# AD637.net
KiCad netlist of a schematic drawn in Altium Designer
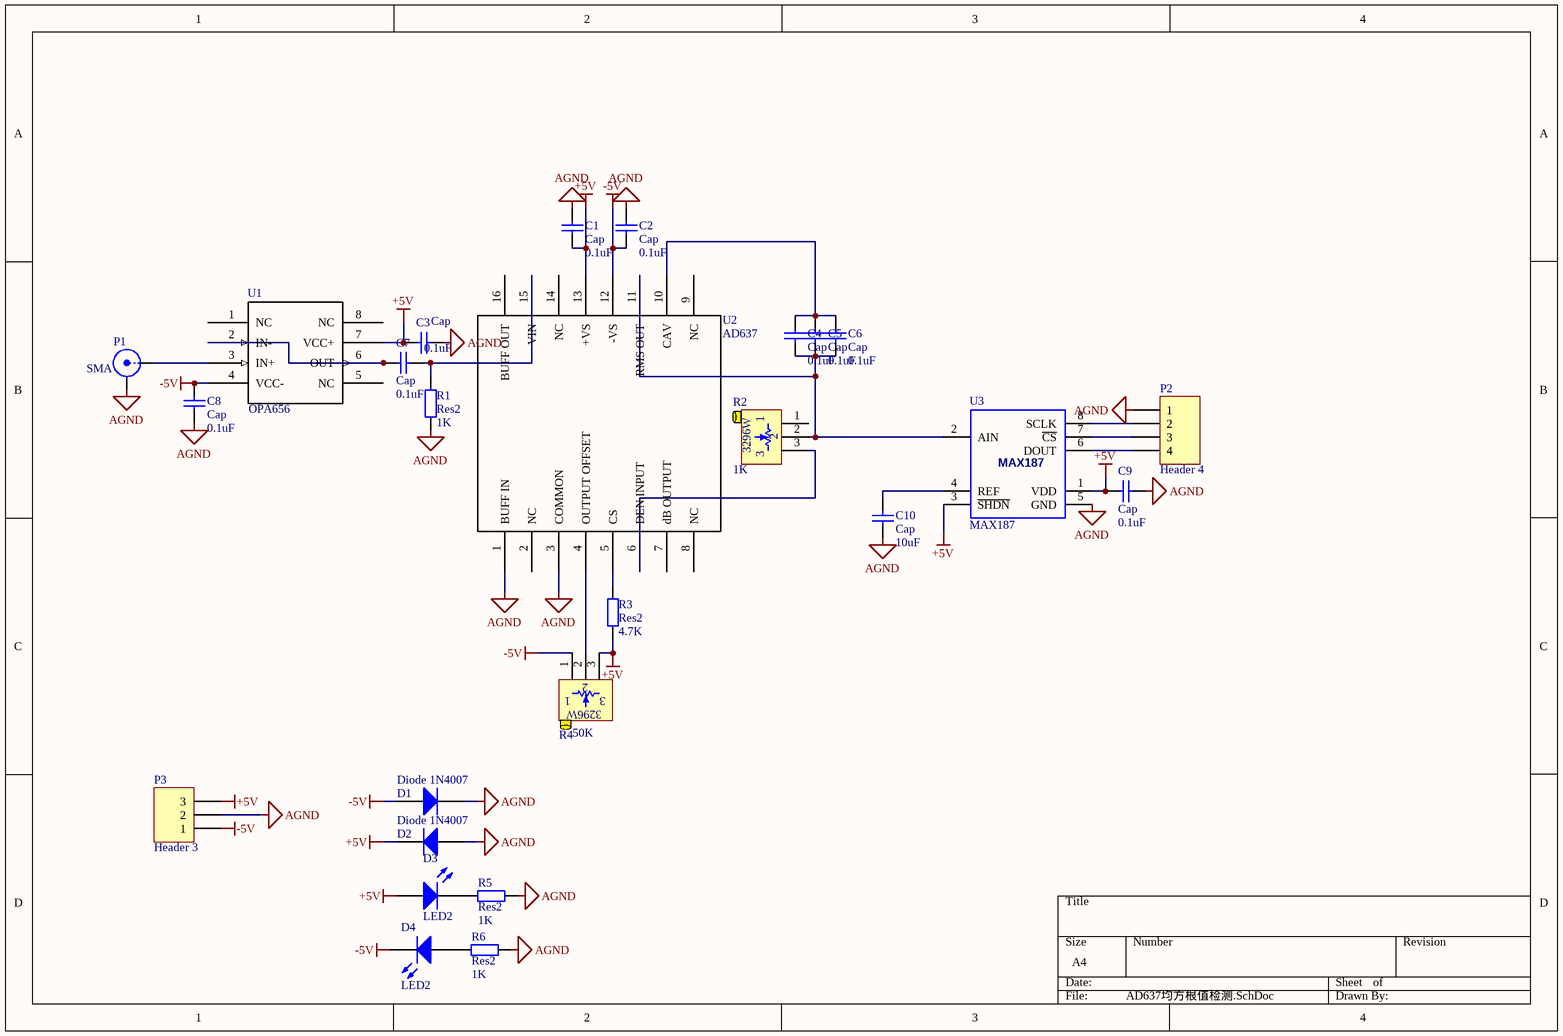
[diagram p0: AD637均方根值检测.SchDoc]

(export (version "E")
  (design (tool "Eeschema 10.0.6"))
  (components
    (comp (ref "C1")
      (value "Cap")
      (footprint "0805")
      (description "Capacitor")
      (fields (field (name "ALTIUM_VALUE") "0.1uF") (field (name "PUBLISHER") "Altium Limited"))
      (libsource (lib "Miscellaneous Devices") (part "Cap"))
    )
    (comp (ref "C2")
      (value "Cap")
      (footprint "0805")
      (description "Capacitor")
      (fields (field (name "ALTIUM_VALUE") "0.1uF") (field (name "PUBLISHER") "Altium Limited"))
      (libsource (lib "Miscellaneous Devices") (part "Cap"))
    )
    (comp (ref "C3")
      (value "Cap")
      (footprint "0805")
      (description "Capacitor")
      (fields (field (name "ALTIUM_VALUE") "0.1uF") (field (name "PUBLISHER") "Altium Limited"))
      (libsource (lib "Miscellaneous Devices") (part "Cap"))
    )
    (comp (ref "C4")
      (value "Cap")
      (footprint "0805")
      (description "Capacitor")
      (fields (field (name "ALTIUM_VALUE") "0.1uF") (field (name "PUBLISHER") "Altium Limited"))
      (libsource (lib "Miscellaneous Devices") (part "Cap"))
    )
    (comp (ref "C5")
      (value "Cap")
      (footprint "0805")
      (description "Capacitor")
      (fields (field (name "ALTIUM_VALUE") "0.1uF") (field (name "PUBLISHER") "Altium Limited"))
      (libsource (lib "Miscellaneous Devices") (part "Cap"))
    )
    (comp (ref "C6")
      (value "Cap")
      (footprint "0805")
      (description "Capacitor")
      (fields (field (name "ALTIUM_VALUE") "0.1uF") (field (name "PUBLISHER") "Altium Limited"))
      (libsource (lib "Miscellaneous Devices") (part "Cap"))
    )
    (comp (ref "C7")
      (value "Cap")
      (footprint "0805")
      (description "Capacitor")
      (fields (field (name "ALTIUM_VALUE") "0.1uF") (field (name "PUBLISHER") "Altium Limited"))
      (libsource (lib "Miscellaneous Devices") (part "Cap"))
    )
    (comp (ref "C8")
      (value "Cap")
      (footprint "0805")
      (description "Capacitor")
      (fields (field (name "ALTIUM_VALUE") "0.1uF") (field (name "PUBLISHER") "Altium Limited"))
      (libsource (lib "Miscellaneous Devices") (part "Cap"))
    )
    (comp (ref "C9")
      (value "Cap")
      (footprint "0805")
      (description "Capacitor")
      (fields (field (name "ALTIUM_VALUE") "0.1uF") (field (name "PUBLISHER") "Altium Limited"))
      (libsource (lib "Miscellaneous Devices") (part "Cap"))
    )
    (comp (ref "C10")
      (value "Cap")
      (footprint "0805")
      (description "Capacitor")
      (fields (field (name "ALTIUM_VALUE") "10uF") (field (name "PUBLISHER") "Altium Limited"))
      (libsource (lib "Miscellaneous Devices") (part "Cap"))
    )
    (comp (ref "D1")
      (value "Diode 1N4007")
      (footprint "0805")
      (description "1 Amp General Purpose Rectifier")
      (fields (field (name "PUBLISHER") "Altium Limited"))
      (libsource (lib "Miscellaneous Devices") (part "Diode 1N4007"))
    )
    (comp (ref "D2")
      (value "Diode 1N4007")
      (footprint "0805")
      (description "1 Amp General Purpose Rectifier")
      (fields (field (name "PUBLISHER") "Altium Limited"))
      (libsource (lib "Miscellaneous Devices") (part "Diode 1N4007"))
    )
    (comp (ref "D3")
      (value "LED2")
      (footprint "3.2X1.6X1.1")
      (description "Typical RED, GREEN, YELLOW, AMBER GaAs LED")
      (fields (field (name "PUBLISHER") "Altium Limited"))
      (libsource (lib "Miscellaneous Devices") (part "LED2"))
    )
    (comp (ref "D4")
      (value "LED2")
      (footprint "3.2X1.6X1.1")
      (description "Typical RED, GREEN, YELLOW, AMBER GaAs LED")
      (fields (field (name "PUBLISHER") "Altium Limited"))
      (libsource (lib "Miscellaneous Devices") (part "LED2"))
    )
    (comp (ref "P1") (value "SMA") (footprint "SMA") (libsource (lib "孙文丰") (part "SMA")))
    (comp (ref "P2")
      (value "Header 4")
      (footprint "HDR1X4")
      (description "Header, 4-Pin")
      (fields (field (name "PUBLISHER") "Altium Limited"))
      (libsource (lib "Miscellaneous Connectors") (part "Header 4"))
    )
    (comp (ref "P3")
      (value "Header 3")
      (footprint "3P排针")
      (description "Header, 3-Pin")
      (fields (field (name "PUBLISHER") "Altium Limited"))
      (libsource (lib "Miscellaneous Connectors") (part "Header 3"))
    )
    (comp (ref "R1")
      (value "Res2")
      (footprint "0805")
      (description "Resistor")
      (fields (field (name "ALTIUM_VALUE") "1K") (field (name "PUBLISHER") "Altium Limited"))
      (libsource (lib "Miscellaneous Devices") (part "Res2"))
    )
    (comp (ref "R2") (value "1K") (footprint "3P排针") (libsource (lib "") (part "电位器_3296W_1")))
    (comp (ref "R3")
      (value "Res2")
      (footprint "0805")
      (description "Resistor")
      (fields (field (name "ALTIUM_VALUE") "4.7K") (field (name "PUBLISHER") "Altium Limited"))
      (libsource (lib "") (part "Res2_2"))
    )
    (comp (ref "R4") (value "50K") (footprint "3P排针") (libsource (lib "常用器件集成库") (part "电位器_3296W")))
    (comp (ref "R5")
      (value "Res2")
      (footprint "0805")
      (description "Resistor")
      (fields (field (name "ALTIUM_VALUE") "1K") (field (name "PUBLISHER") "Altium Limited"))
      (libsource (lib "") (part "Res2_1"))
    )
    (comp (ref "R6")
      (value "Res2")
      (footprint "0805")
      (description "Resistor")
      (fields (field (name "ALTIUM_VALUE") "1K") (field (name "PUBLISHER") "Altium Limited"))
      (libsource (lib "") (part "Res2_1"))
    )
    (comp (ref "U1")
      (value "OPA656")
      (footprint "THS3001_SOIC")
      (libsource (lib "MY_TI_Library") (part "OPA656"))
    )
    (comp (ref "U2")
      (value "AD637")
      (footprint "AD637_SOIC")
      (libsource (lib "MY_TI_Library") (part "AD637"))
    )
    (comp (ref "U3")
      (value "MAX187")
      (footprint "DIP8")
      (description "+5V、低功耗、12位串行ADC")
      (libsource (lib "常用器件集成库") (part "MAX187"))
    )
  )
  (nets
    (net (code "1") (name "+5V") (class "Default")
      (node (ref "C1") (pin "2") (pinfunction "2_2") (pintype "passive"))
      (node (ref "C3") (pin "1") (pinfunction "1_1") (pintype "passive"))
      (node (ref "C9") (pin "1") (pinfunction "1_1") (pintype "passive"))
      (node (ref "D2") (pin "2") (pinfunction "K_2") (pintype "passive"))
      (node (ref "D3") (pin "1") (pinfunction "A_1") (pintype "passive"))
      (node (ref "P3") (pin "3") (pinfunction "3_3") (pintype "passive"))
      (node (ref "R3") (pin "2") (pinfunction "2_2") (pintype "passive"))
      (node (ref "R4") (pin "3") (pintype "passive"))
      (node (ref "U1") (pin "7") (pinfunction "VCC+_7") (pintype "power_in"))
      (node (ref "U2") (pin "13") (pinfunction "+VS_13") (pintype "power_in"))
      (node (ref "U3") (pin "1") (pinfunction "VDD_1") (pintype "passive"))
      (node (ref "U3") (pin "3") (pinfunction "~{SHDN}_3") (pintype "passive"))
    )
    (net (code "2") (name "-5V") (class "Default")
      (node (ref "C2") (pin "2") (pinfunction "2_2") (pintype "passive"))
      (node (ref "C8") (pin "1") (pinfunction "1_1") (pintype "passive"))
      (node (ref "D1") (pin "1") (pinfunction "A_1") (pintype "passive"))
      (node (ref "D4") (pin "2") (pinfunction "K_2") (pintype "passive"))
      (node (ref "P3") (pin "1") (pinfunction "1_1") (pintype "passive"))
      (node (ref "R4") (pin "1") (pintype "passive"))
      (node (ref "U1") (pin "4") (pinfunction "VCC-_4") (pintype "power_in"))
      (node (ref "U2") (pin "12") (pinfunction "-VS_12") (pintype "power_in"))
    )
    (net (code "3") (name "AGND") (class "Default")
      (node (ref "C1") (pin "1") (pinfunction "1_1") (pintype "passive"))
      (node (ref "C10") (pin "1") (pinfunction "1_1") (pintype "passive"))
      (node (ref "C2") (pin "1") (pinfunction "1_1") (pintype "passive"))
      (node (ref "C3") (pin "2") (pinfunction "2_2") (pintype "passive"))
      (node (ref "C8") (pin "2") (pinfunction "2_2") (pintype "passive"))
      (node (ref "C9") (pin "2") (pinfunction "2_2") (pintype "passive"))
      (node (ref "D1") (pin "2") (pinfunction "K_2") (pintype "passive"))
      (node (ref "D2") (pin "1") (pinfunction "A_1") (pintype "passive"))
      (node (ref "P1") (pin "2") (pinfunction "Y_2") (pintype "passive"))
      (node (ref "P2") (pin "1") (pinfunction "1_1") (pintype "passive"))
      (node (ref "P3") (pin "2") (pinfunction "2_2") (pintype "passive"))
      (node (ref "R1") (pin "1") (pinfunction "1_1") (pintype "passive"))
      (node (ref "R5") (pin "2") (pinfunction "2_2") (pintype "passive"))
      (node (ref "R6") (pin "2") (pinfunction "2_2") (pintype "passive"))
      (node (ref "U2") (pin "1") (pinfunction "BUFF_IN_1") (pintype "passive"))
      (node (ref "U2") (pin "3") (pinfunction "COMMON_3") (pintype "passive"))
      (node (ref "U3") (pin "5") (pinfunction "GND_5") (pintype "passive"))
    )
    (net (code "4") (name "Net-(D3-K)") (class "Default")
      (node (ref "D3") (pin "2") (pinfunction "K_2") (pintype "passive"))
      (node (ref "R5") (pin "1") (pinfunction "1_1") (pintype "passive"))
    )
    (net (code "5") (name "Net-(D4-A)") (class "Default")
      (node (ref "D4") (pin "1") (pinfunction "A_1") (pintype "passive"))
      (node (ref "R6") (pin "1") (pinfunction "1_1") (pintype "passive"))
    )
    (net (code "6") (name "Net-(P1-X)") (class "Default")
      (node (ref "P1") (pin "1") (pinfunction "X_1") (pintype "passive"))
      (node (ref "U1") (pin "3") (pinfunction "IN+_3") (pintype "input"))
    )
    (net (code "7") (name "Net-(U1-IN-)") (class "Default")
      (node (ref "C7") (pin "1") (pinfunction "1_1") (pintype "passive"))
      (node (ref "U1") (pin "2") (pinfunction "IN-_2") (pintype "input"))
      (node (ref "U1") (pin "6") (pinfunction "OUT_6") (pintype "output"))
    )
    (net (code "8") (name "Net-(U2-CAV)") (class "Default")
      (node (ref "C4") (pin "2") (pinfunction "2_2") (pintype "passive"))
      (node (ref "C5") (pin "2") (pinfunction "2_2") (pintype "passive"))
      (node (ref "C6") (pin "2") (pinfunction "2_2") (pintype "passive"))
      (node (ref "U2") (pin "10") (pinfunction "CAV_10") (pintype "passive"))
    )
    (net (code "9") (name "Net-(U2-CS)") (class "Default")
      (node (ref "R3") (pin "1") (pinfunction "1_1") (pintype "passive"))
      (node (ref "U2") (pin "5") (pinfunction "CS_5") (pintype "passive"))
    )
    (net (code "10") (name "Net-(U2-DEN_INPUT)") (class "Default")
      (node (ref "R2") (pin "3") (pintype "passive"))
      (node (ref "U2") (pin "6") (pinfunction "DEN_INPUT_6") (pintype "passive"))
    )
    (net (code "11") (name "Net-(U2-OUTPUT_OFFSET)") (class "Default")
      (node (ref "R4") (pin "2") (pintype "passive"))
      (node (ref "U2") (pin "4") (pinfunction "OUTPUT_OFFSET_4") (pintype "passive"))
    )
    (net (code "12") (name "Net-(U2-RMS_OUT)") (class "Default")
      (node (ref "C4") (pin "1") (pinfunction "1_1") (pintype "passive"))
      (node (ref "C5") (pin "1") (pinfunction "1_1") (pintype "passive"))
      (node (ref "C6") (pin "1") (pinfunction "1_1") (pintype "passive"))
      (node (ref "R2") (pin "2") (pintype "passive"))
      (node (ref "U2") (pin "11") (pinfunction "RMS_OUT_11") (pintype "passive"))
      (node (ref "U3") (pin "2") (pinfunction "AIN_2") (pintype "passive"))
    )
    (net (code "13") (name "Net-(U2-VIN)") (class "Default")
      (node (ref "C7") (pin "2") (pinfunction "2_2") (pintype "passive"))
      (node (ref "R1") (pin "2") (pinfunction "2_2") (pintype "passive"))
      (node (ref "U2") (pin "15") (pinfunction "VIN_15") (pintype "passive"))
    )
    (net (code "14") (name "Net-(U3-DOUT)") (class "Default")
      (node (ref "P2") (pin "4") (pinfunction "4_4") (pintype "passive"))
      (node (ref "U3") (pin "6") (pinfunction "DOUT_6") (pintype "passive"))
    )
    (net (code "15") (name "Net-(U3-REF)") (class "Default")
      (node (ref "C10") (pin "2") (pinfunction "2_2") (pintype "passive"))
      (node (ref "U3") (pin "4") (pinfunction "REF_4") (pintype "passive"))
    )
    (net (code "16") (name "Net-(U3-SCLK)") (class "Default")
      (node (ref "P2") (pin "2") (pinfunction "2_2") (pintype "passive"))
      (node (ref "U3") (pin "8") (pinfunction "SCLK_8") (pintype "passive"))
    )
    (net (code "17") (name "Net-(U3-~{CS})") (class "Default")
      (node (ref "P2") (pin "3") (pinfunction "3_3") (pintype "passive"))
      (node (ref "U3") (pin "7") (pinfunction "~{CS}_7") (pintype "passive"))
    )
    (net (code "18") (name "unconnected-(R2-Pad1)") (class "Default")
      (node (ref "R2") (pin "1") (pintype "passive"))
    )
    (net (code "19") (name "unconnected-(U1-NC-Pad1)") (class "Default")
      (node (ref "U1") (pin "1") (pinfunction "NC_1") (pintype "passive"))
    )
    (net (code "20") (name "unconnected-(U1-NC-Pad5)") (class "Default")
      (node (ref "U1") (pin "5") (pinfunction "NC_5") (pintype "passive"))
    )
    (net (code "21") (name "unconnected-(U1-NC-Pad8)") (class "Default")
      (node (ref "U1") (pin "8") (pinfunction "NC_8") (pintype "passive"))
    )
    (net (code "22") (name "unconnected-(U2-BUFF_OUT-Pad16)") (class "Default")
      (node (ref "U2") (pin "16") (pinfunction "BUFF_OUT_16") (pintype "passive"))
    )
    (net (code "23") (name "unconnected-(U2-NC-Pad2)") (class "Default")
      (node (ref "U2") (pin "2") (pinfunction "NC_2") (pintype "passive"))
    )
    (net (code "24") (name "unconnected-(U2-NC-Pad8)") (class "Default")
      (node (ref "U2") (pin "8") (pinfunction "NC_8") (pintype "passive"))
    )
    (net (code "25") (name "unconnected-(U2-NC-Pad9)") (class "Default")
      (node (ref "U2") (pin "9") (pinfunction "NC_9") (pintype "passive"))
    )
    (net (code "26") (name "unconnected-(U2-NC-Pad14)") (class "Default")
      (node (ref "U2") (pin "14") (pinfunction "NC_14") (pintype "passive"))
    )
    (net (code "27") (name "unconnected-(U2-dB_OUTPUT-Pad7)") (class "Default")
      (node (ref "U2") (pin "7") (pinfunction "dB_OUTPUT_7") (pintype "passive"))
    )
  )
)
